# Connector.net
KiCad netlist of a schematic drawn in Altium Designer
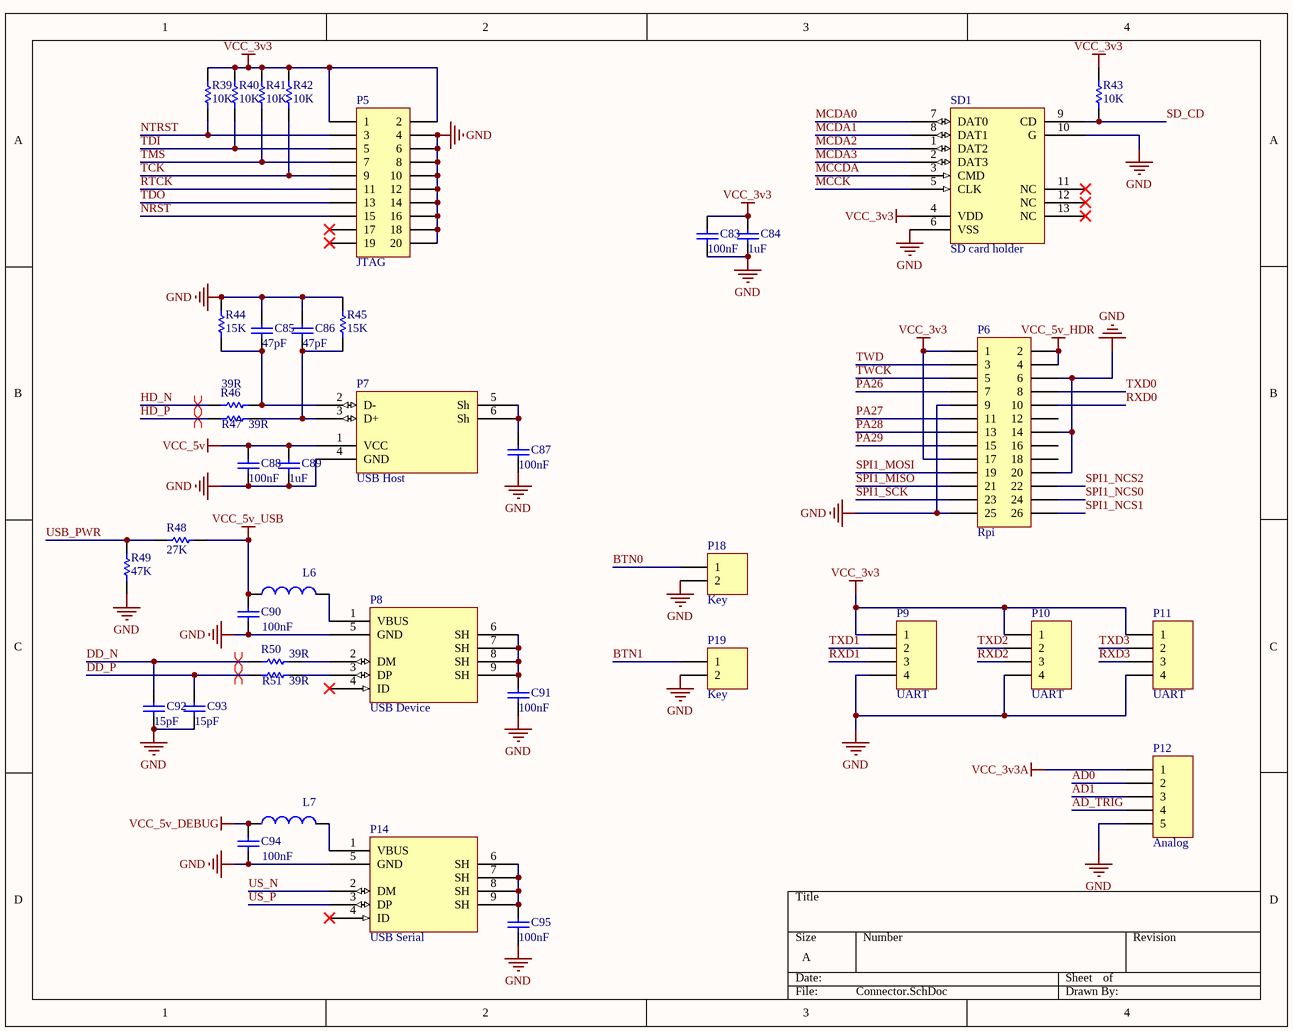
[diagram p0: Connector.SchDoc]

(export (version "E")
  (design (tool "Eeschema 10.0.6"))
  (components
    (comp (ref "C83")
      (value "100nF")
      (footprint "C0805")
      (description "Capacitor")
      (fields (field (name "Comment") "Cap") (field (name "PUBLISHER") "Altium Limited"))
      (libsource (lib "Miscellaneous Devices") (part "Cap"))
    )
    (comp (ref "C84")
      (value "1uF")
      (footprint "C0805")
      (description "Capacitor")
      (fields (field (name "Comment") "Cap") (field (name "PUBLISHER") "Altium Limited"))
      (libsource (lib "Miscellaneous Devices") (part "Cap"))
    )
    (comp (ref "C85")
      (value "47pF")
      (footprint "C0805")
      (description "Capacitor")
      (fields (field (name "Comment") "Cap") (field (name "PUBLISHER") "Altium Limited"))
      (libsource (lib "Miscellaneous Devices") (part "Cap"))
    )
    (comp (ref "C86")
      (value "47pF")
      (footprint "C0805")
      (description "Capacitor")
      (fields (field (name "Comment") "Cap") (field (name "PUBLISHER") "Altium Limited"))
      (libsource (lib "Miscellaneous Devices") (part "Cap"))
    )
    (comp (ref "C87")
      (value "100nF")
      (footprint "C0805")
      (description "Capacitor")
      (fields (field (name "Comment") "Cap") (field (name "PUBLISHER") "Altium Limited"))
      (libsource (lib "Miscellaneous Devices") (part "Cap"))
    )
    (comp (ref "C88")
      (value "100nF")
      (footprint "C0805")
      (description "Capacitor")
      (fields (field (name "Comment") "Cap") (field (name "PUBLISHER") "Altium Limited"))
      (libsource (lib "Miscellaneous Devices") (part "Cap"))
    )
    (comp (ref "C89")
      (value "1uF")
      (footprint "C0805")
      (description "Capacitor")
      (fields (field (name "Comment") "Cap") (field (name "PUBLISHER") "Altium Limited"))
      (libsource (lib "Miscellaneous Devices") (part "Cap"))
    )
    (comp (ref "C90")
      (value "100nF")
      (footprint "C0805")
      (description "Capacitor")
      (fields (field (name "Comment") "Cap") (field (name "PUBLISHER") "Altium Limited"))
      (libsource (lib "Miscellaneous Devices") (part "Cap"))
    )
    (comp (ref "C91")
      (value "100nF")
      (footprint "C0805")
      (description "Capacitor")
      (fields (field (name "Comment") "Cap") (field (name "PUBLISHER") "Altium Limited"))
      (libsource (lib "Miscellaneous Devices") (part "Cap"))
    )
    (comp (ref "C92")
      (value "15pF")
      (footprint "C0805")
      (description "Capacitor")
      (fields (field (name "Comment") "Cap") (field (name "PUBLISHER") "Altium Limited"))
      (libsource (lib "Miscellaneous Devices") (part "Cap"))
    )
    (comp (ref "C93")
      (value "15pF")
      (footprint "C0805")
      (description "Capacitor")
      (fields (field (name "Comment") "Cap") (field (name "PUBLISHER") "Altium Limited"))
      (libsource (lib "Miscellaneous Devices") (part "Cap"))
    )
    (comp (ref "C94")
      (value "100nF")
      (footprint "C0805")
      (description "Capacitor")
      (fields (field (name "Comment") "Cap") (field (name "PUBLISHER") "Altium Limited"))
      (libsource (lib "Miscellaneous Devices") (part "Cap"))
    )
    (comp (ref "C95")
      (value "100nF")
      (footprint "C0805")
      (description "Capacitor")
      (fields (field (name "Comment") "Cap") (field (name "PUBLISHER") "Altium Limited"))
      (libsource (lib "Miscellaneous Devices") (part "Cap"))
    )
    (comp (ref "L6")
      (value "Ferrite Bead")
      (footprint "C0805")
      (description "Inductor")
      (fields (field (name "PUBLISHER") "Altium Limited"))
      (libsource (lib "Miscellaneous Devices") (part "Inductor"))
    )
    (comp (ref "L7")
      (value "Ferrite Bead")
      (footprint "C0805")
      (description "Inductor")
      (fields (field (name "PUBLISHER") "Altium Limited"))
      (libsource (lib "Miscellaneous Devices") (part "Inductor"))
    )
    (comp (ref "P5")
      (value "JTAG")
      (footprint "IDC_2X10")
      (description "Header, 10-Pin, Dual row")
      (fields (field (name "PUBLISHER") "Altium Limited"))
      (libsource (lib "Miscellaneous Connectors") (part "Header 10X2"))
    )
    (comp (ref "P6")
      (value "Rpi")
      (footprint "HDR2X13")
      (description "Header, 13-Pin, Dual row")
      (fields (field (name "PUBLISHER") "Altium Limited"))
      (libsource (lib "Miscellaneous Connectors") (part "Header 13X2"))
    )
    (comp (ref "P7")
      (value "USB Host")
      (footprint "USB_Female")
      (libsource (lib "Connector_IntLib") (part "USB Host"))
    )
    (comp (ref "P8")
      (value "USB Device")
      (footprint "Mini USB")
      (libsource (lib "Connector_IntLib") (part "Mini USB"))
    )
    (comp (ref "P9")
      (value "UART")
      (footprint "XH_4pin")
      (description "Header, 4-Pin")
      (fields (field (name "PUBLISHER") "Altium Limited"))
      (libsource (lib "Miscellaneous Connectors") (part "Header 4"))
    )
    (comp (ref "P10")
      (value "UART")
      (footprint "XH_4pin")
      (description "Header, 4-Pin")
      (fields (field (name "PUBLISHER") "Altium Limited"))
      (libsource (lib "Miscellaneous Connectors") (part "Header 4"))
    )
    (comp (ref "P11")
      (value "UART")
      (footprint "XH_4pin")
      (description "Header, 4-Pin")
      (fields (field (name "PUBLISHER") "Altium Limited"))
      (libsource (lib "Miscellaneous Connectors") (part "Header 4"))
    )
    (comp (ref "P12")
      (value "Analog")
      (footprint "XH_5pin")
      (description "Header, 5-Pin")
      (fields (field (name "PUBLISHER") "Altium Limited"))
      (libsource (lib "Miscellaneous Connectors") (part "Header 5"))
    )
    (comp (ref "P14")
      (value "USB Serial")
      (footprint "Mini USB")
      (libsource (lib "Connector_IntLib") (part "Mini USB"))
    )
    (comp (ref "P18")
      (value "Key")
      (footprint "HDR1X2")
      (description "Header, 2-Pin")
      (fields (field (name "PUBLISHER") "Altium Limited"))
      (libsource (lib "Miscellaneous Connectors") (part "Header 2"))
    )
    (comp (ref "P19")
      (value "Key")
      (footprint "HDR1X2")
      (description "Header, 2-Pin")
      (fields (field (name "PUBLISHER") "Altium Limited"))
      (libsource (lib "Miscellaneous Connectors") (part "Header 2"))
    )
    (comp (ref "R39")
      (value "10K")
      (footprint "C0805")
      (description "Semiconductor Resistor")
      (fields (field (name "Comment") "Res Semi") (field (name "PUBLISHER") "Altium Limited"))
      (libsource (lib "Miscellaneous Devices") (part "Res Semi"))
    )
    (comp (ref "R40")
      (value "10K")
      (footprint "C0805")
      (description "Semiconductor Resistor")
      (fields (field (name "Comment") "Res Semi") (field (name "PUBLISHER") "Altium Limited"))
      (libsource (lib "Miscellaneous Devices") (part "Res Semi"))
    )
    (comp (ref "R41")
      (value "10K")
      (footprint "C0805")
      (description "Semiconductor Resistor")
      (fields (field (name "Comment") "Res Semi") (field (name "PUBLISHER") "Altium Limited"))
      (libsource (lib "Miscellaneous Devices") (part "Res Semi"))
    )
    (comp (ref "R42")
      (value "10K")
      (footprint "C0805")
      (description "Semiconductor Resistor")
      (fields (field (name "Comment") "Res Semi") (field (name "PUBLISHER") "Altium Limited"))
      (libsource (lib "Miscellaneous Devices") (part "Res Semi"))
    )
    (comp (ref "R43")
      (value "10K")
      (footprint "C0805")
      (description "Semiconductor Resistor")
      (fields (field (name "Comment") "Res Semi") (field (name "PUBLISHER") "Altium Limited"))
      (libsource (lib "Miscellaneous Devices") (part "Res Semi"))
    )
    (comp (ref "R44")
      (value "15K")
      (footprint "C0805")
      (description "Semiconductor Resistor")
      (fields (field (name "Comment") "Res Semi") (field (name "PUBLISHER") "Altium Limited"))
      (libsource (lib "Miscellaneous Devices") (part "Res Semi"))
    )
    (comp (ref "R45")
      (value "15K")
      (footprint "C0805")
      (description "Semiconductor Resistor")
      (fields (field (name "Comment") "Res Semi") (field (name "PUBLISHER") "Altium Limited"))
      (libsource (lib "Miscellaneous Devices") (part "Res Semi"))
    )
    (comp (ref "R46")
      (value "39R")
      (footprint "C0805")
      (description "Semiconductor Resistor")
      (fields (field (name "Comment") "Res Semi") (field (name "PUBLISHER") "Altium Limited"))
      (libsource (lib "Miscellaneous Devices") (part "Res Semi"))
    )
    (comp (ref "R47")
      (value "39R")
      (footprint "C0805")
      (description "Semiconductor Resistor")
      (fields (field (name "Comment") "Res Semi") (field (name "PUBLISHER") "Altium Limited"))
      (libsource (lib "Miscellaneous Devices") (part "Res Semi"))
    )
    (comp (ref "R48")
      (value "27K")
      (footprint "C0805")
      (description "Semiconductor Resistor")
      (fields (field (name "Comment") "Res Semi") (field (name "PUBLISHER") "Altium Limited"))
      (libsource (lib "Miscellaneous Devices") (part "Res Semi"))
    )
    (comp (ref "R49")
      (value "47K")
      (footprint "C0805")
      (description "Semiconductor Resistor")
      (fields (field (name "Comment") "Res Semi") (field (name "PUBLISHER") "Altium Limited"))
      (libsource (lib "Miscellaneous Devices") (part "Res Semi"))
    )
    (comp (ref "R50")
      (value "39R")
      (footprint "C0805")
      (description "Semiconductor Resistor")
      (fields (field (name "Comment") "Res Semi") (field (name "PUBLISHER") "Altium Limited"))
      (libsource (lib "Miscellaneous Devices") (part "Res Semi"))
    )
    (comp (ref "R51")
      (value "39R")
      (footprint "C0805")
      (description "Semiconductor Resistor")
      (fields (field (name "Comment") "Res Semi") (field (name "PUBLISHER") "Altium Limited"))
      (libsource (lib "Miscellaneous Devices") (part "Res Semi"))
    )
    (comp (ref "SD1")
      (value "SD card holder")
      (footprint "MicroSD socket")
      (libsource (lib "Connector_IntLib") (part "MicroSD_holder"))
    )
  )
  (nets
    (net (code "1") (name "/AD0") (class "Default")
      (node (ref "P12") (pin "2") (pinfunction "2_2") (pintype "passive"))
    )
    (net (code "2") (name "/AD1") (class "Default")
      (node (ref "P12") (pin "3") (pinfunction "3_3") (pintype "passive"))
    )
    (net (code "3") (name "/AD_TRIG") (class "Default")
      (node (ref "P12") (pin "4") (pinfunction "4_4") (pintype "passive"))
    )
    (net (code "4") (name "/BTN0") (class "Default")
      (node (ref "P18") (pin "1") (pinfunction "1_1") (pintype "passive"))
    )
    (net (code "5") (name "/BTN1") (class "Default")
      (node (ref "P19") (pin "1") (pinfunction "1_1") (pintype "passive"))
    )
    (net (code "6") (name "/DD_N") (class "Default")
      (node (ref "C92") (pin "2") (pinfunction "2_2") (pintype "passive"))
      (node (ref "R50") (pin "1") (pinfunction "1_1") (pintype "passive"))
    )
    (net (code "7") (name "/DD_P") (class "Default")
      (node (ref "C93") (pin "2") (pinfunction "2_2") (pintype "passive"))
      (node (ref "R51") (pin "1") (pinfunction "1_1") (pintype "passive"))
    )
    (net (code "8") (name "/HD_N") (class "Default")
      (node (ref "R46") (pin "1") (pinfunction "1_1") (pintype "passive"))
    )
    (net (code "9") (name "/HD_P") (class "Default")
      (node (ref "R47") (pin "1") (pinfunction "1_1") (pintype "passive"))
    )
    (net (code "10") (name "/MCCDA") (class "Default")
      (node (ref "SD1") (pin "3") (pinfunction "CMD_3") (pintype "input"))
    )
    (net (code "11") (name "/MCCK") (class "Default")
      (node (ref "SD1") (pin "5") (pinfunction "CLK_5") (pintype "input"))
    )
    (net (code "12") (name "/MCDA0") (class "Default")
      (node (ref "SD1") (pin "7") (pinfunction "DAT0_7") (pintype "bidirectional"))
    )
    (net (code "13") (name "/MCDA1") (class "Default")
      (node (ref "SD1") (pin "8") (pinfunction "DAT1_8") (pintype "bidirectional"))
    )
    (net (code "14") (name "/MCDA2") (class "Default")
      (node (ref "SD1") (pin "1") (pinfunction "DAT2_1") (pintype "bidirectional"))
    )
    (net (code "15") (name "/MCDA3") (class "Default")
      (node (ref "SD1") (pin "2") (pinfunction "DAT3_2") (pintype "bidirectional"))
    )
    (net (code "16") (name "/NRST") (class "Default")
      (node (ref "P5") (pin "15") (pinfunction "15_15") (pintype "passive"))
    )
    (net (code "17") (name "/NTRST") (class "Default")
      (node (ref "P5") (pin "3") (pinfunction "3_3") (pintype "passive"))
      (node (ref "R39") (pin "2") (pinfunction "2_2") (pintype "passive"))
    )
    (net (code "18") (name "/PA26") (class "Default")
      (node (ref "P6") (pin "7") (pinfunction "7_7") (pintype "passive"))
    )
    (net (code "19") (name "/PA27") (class "Default")
      (node (ref "P6") (pin "11") (pinfunction "11_11") (pintype "passive"))
    )
    (net (code "20") (name "/PA28") (class "Default")
      (node (ref "P6") (pin "13") (pinfunction "13_13") (pintype "passive"))
    )
    (net (code "21") (name "/PA29") (class "Default")
      (node (ref "P6") (pin "15") (pinfunction "15_15") (pintype "passive"))
    )
    (net (code "22") (name "/RTCK") (class "Default")
      (node (ref "P5") (pin "11") (pinfunction "11_11") (pintype "passive"))
    )
    (net (code "23") (name "/RXD0") (class "Default")
      (node (ref "P6") (pin "10") (pinfunction "10_10") (pintype "passive"))
    )
    (net (code "24") (name "/RXD1") (class "Default")
      (node (ref "P9") (pin "3") (pinfunction "3_3") (pintype "passive"))
    )
    (net (code "25") (name "/RXD2") (class "Default")
      (node (ref "P10") (pin "3") (pinfunction "3_3") (pintype "passive"))
    )
    (net (code "26") (name "/RXD3") (class "Default")
      (node (ref "P11") (pin "3") (pinfunction "3_3") (pintype "passive"))
    )
    (net (code "27") (name "/SD_CD") (class "Default")
      (node (ref "R43") (pin "2") (pinfunction "2_2") (pintype "passive"))
      (node (ref "SD1") (pin "9") (pinfunction "CD_9") (pintype "passive"))
    )
    (net (code "28") (name "/SPI1_MISO") (class "Default")
      (node (ref "P6") (pin "21") (pinfunction "21_21") (pintype "passive"))
    )
    (net (code "29") (name "/SPI1_MOSI") (class "Default")
      (node (ref "P6") (pin "19") (pinfunction "19_19") (pintype "passive"))
    )
    (net (code "30") (name "/SPI1_NCS0") (class "Default")
      (node (ref "P6") (pin "24") (pinfunction "24_24") (pintype "passive"))
    )
    (net (code "31") (name "/SPI1_NCS1") (class "Default")
      (node (ref "P6") (pin "26") (pinfunction "26_26") (pintype "passive"))
    )
    (net (code "32") (name "/SPI1_NCS2") (class "Default")
      (node (ref "P6") (pin "22") (pinfunction "22_22") (pintype "passive"))
    )
    (net (code "33") (name "/SPI1_SCK") (class "Default")
      (node (ref "P6") (pin "23") (pinfunction "23_23") (pintype "passive"))
    )
    (net (code "34") (name "/TCK") (class "Default")
      (node (ref "P5") (pin "9") (pinfunction "9_9") (pintype "passive"))
      (node (ref "R42") (pin "2") (pinfunction "2_2") (pintype "passive"))
    )
    (net (code "35") (name "/TDI") (class "Default")
      (node (ref "P5") (pin "5") (pinfunction "5_5") (pintype "passive"))
      (node (ref "R40") (pin "2") (pinfunction "2_2") (pintype "passive"))
    )
    (net (code "36") (name "/TDO") (class "Default")
      (node (ref "P5") (pin "13") (pinfunction "13_13") (pintype "passive"))
    )
    (net (code "37") (name "/TMS") (class "Default")
      (node (ref "P5") (pin "7") (pinfunction "7_7") (pintype "passive"))
      (node (ref "R41") (pin "2") (pinfunction "2_2") (pintype "passive"))
    )
    (net (code "38") (name "/TWCK") (class "Default")
      (node (ref "P6") (pin "5") (pinfunction "5_5") (pintype "passive"))
    )
    (net (code "39") (name "/TWD") (class "Default")
      (node (ref "P6") (pin "3") (pinfunction "3_3") (pintype "passive"))
    )
    (net (code "40") (name "/TXD0") (class "Default")
      (node (ref "P6") (pin "8") (pinfunction "8_8") (pintype "passive"))
    )
    (net (code "41") (name "/TXD1") (class "Default")
      (node (ref "P9") (pin "2") (pinfunction "2_2") (pintype "passive"))
    )
    (net (code "42") (name "/TXD2") (class "Default")
      (node (ref "P10") (pin "2") (pinfunction "2_2") (pintype "passive"))
    )
    (net (code "43") (name "/TXD3") (class "Default")
      (node (ref "P11") (pin "2") (pinfunction "2_2") (pintype "passive"))
    )
    (net (code "44") (name "/USB_PWR") (class "Default")
      (node (ref "R48") (pin "2") (pinfunction "2_2") (pintype "passive"))
      (node (ref "R49") (pin "1") (pinfunction "1_1") (pintype "passive"))
    )
    (net (code "45") (name "/US_N") (class "Default")
      (node (ref "P14") (pin "2") (pinfunction "DM_2") (pintype "bidirectional"))
    )
    (net (code "46") (name "/US_P") (class "Default")
      (node (ref "P14") (pin "3") (pinfunction "DP_3") (pintype "bidirectional"))
    )
    (net (code "47") (name "GND") (class "Default")
      (node (ref "C83") (pin "1") (pinfunction "1_1") (pintype "passive"))
      (node (ref "C84") (pin "1") (pinfunction "1_1") (pintype "passive"))
      (node (ref "C85") (pin "2") (pinfunction "2_2") (pintype "passive"))
      (node (ref "C86") (pin "2") (pinfunction "2_2") (pintype "passive"))
      (node (ref "C87") (pin "1") (pinfunction "1_1") (pintype "passive"))
      (node (ref "C88") (pin "1") (pinfunction "1_1") (pintype "passive"))
      (node (ref "C89") (pin "1") (pinfunction "1_1") (pintype "passive"))
      (node (ref "C90") (pin "1") (pinfunction "1_1") (pintype "passive"))
      (node (ref "C91") (pin "1") (pinfunction "1_1") (pintype "passive"))
      (node (ref "C92") (pin "1") (pinfunction "1_1") (pintype "passive"))
      (node (ref "C93") (pin "1") (pinfunction "1_1") (pintype "passive"))
      (node (ref "C94") (pin "1") (pinfunction "1_1") (pintype "passive"))
      (node (ref "C95") (pin "1") (pinfunction "1_1") (pintype "passive"))
      (node (ref "P10") (pin "4") (pinfunction "4_4") (pintype "passive"))
      (node (ref "P11") (pin "4") (pinfunction "4_4") (pintype "passive"))
      (node (ref "P12") (pin "5") (pinfunction "5_5") (pintype "passive"))
      (node (ref "P14") (pin "5") (pinfunction "GND_5") (pintype "power_in"))
      (node (ref "P18") (pin "2") (pinfunction "2_2") (pintype "passive"))
      (node (ref "P19") (pin "2") (pinfunction "2_2") (pintype "passive"))
      (node (ref "P5") (pin "10") (pinfunction "10_10") (pintype "passive"))
      (node (ref "P5") (pin "12") (pinfunction "12_12") (pintype "passive"))
      (node (ref "P5") (pin "14") (pinfunction "14_14") (pintype "passive"))
      (node (ref "P5") (pin "16") (pinfunction "16_16") (pintype "passive"))
      (node (ref "P5") (pin "18") (pinfunction "18_18") (pintype "passive"))
      (node (ref "P5") (pin "20") (pinfunction "20_20") (pintype "passive"))
      (node (ref "P5") (pin "4") (pinfunction "4_4") (pintype "passive"))
      (node (ref "P5") (pin "6") (pinfunction "6_6") (pintype "passive"))
      (node (ref "P5") (pin "8") (pinfunction "8_8") (pintype "passive"))
      (node (ref "P6") (pin "14") (pinfunction "14_14") (pintype "passive"))
      (node (ref "P6") (pin "20") (pinfunction "20_20") (pintype "passive"))
      (node (ref "P6") (pin "25") (pinfunction "25_25") (pintype "passive"))
      (node (ref "P6") (pin "6") (pinfunction "6_6") (pintype "passive"))
      (node (ref "P6") (pin "9") (pinfunction "9_9") (pintype "passive"))
      (node (ref "P7") (pin "4") (pinfunction "GND_4") (pintype "power_in"))
      (node (ref "P8") (pin "5") (pinfunction "GND_5") (pintype "power_in"))
      (node (ref "P9") (pin "4") (pinfunction "4_4") (pintype "passive"))
      (node (ref "R44") (pin "1") (pinfunction "1_1") (pintype "passive"))
      (node (ref "R45") (pin "1") (pinfunction "1_1") (pintype "passive"))
      (node (ref "R49") (pin "2") (pinfunction "2_2") (pintype "passive"))
      (node (ref "SD1") (pin "10") (pinfunction "G_10") (pintype "passive"))
      (node (ref "SD1") (pin "6") (pinfunction "VSS_6") (pintype "power_in"))
    )
    (net (code "48") (name "Net-(C87-Pad2)") (class "Default")
      (node (ref "C87") (pin "2") (pinfunction "2_2") (pintype "passive"))
      (node (ref "P7") (pin "5") (pinfunction "Sh_5") (pintype "passive"))
      (node (ref "P7") (pin "6") (pinfunction "Sh_6") (pintype "passive"))
    )
    (net (code "49") (name "Net-(C91-Pad2)") (class "Default")
      (node (ref "C91") (pin "2") (pinfunction "2_2") (pintype "passive"))
      (node (ref "P8") (pin "6") (pinfunction "SH_6") (pintype "passive"))
      (node (ref "P8") (pin "7") (pinfunction "SH_7") (pintype "passive"))
      (node (ref "P8") (pin "8") (pinfunction "SH_8") (pintype "passive"))
      (node (ref "P8") (pin "9") (pinfunction "SH_9") (pintype "passive"))
    )
    (net (code "50") (name "Net-(C95-Pad2)") (class "Default")
      (node (ref "C95") (pin "2") (pinfunction "2_2") (pintype "passive"))
      (node (ref "P14") (pin "6") (pinfunction "SH_6") (pintype "passive"))
      (node (ref "P14") (pin "7") (pinfunction "SH_7") (pintype "passive"))
      (node (ref "P14") (pin "8") (pinfunction "SH_8") (pintype "passive"))
      (node (ref "P14") (pin "9") (pinfunction "SH_9") (pintype "passive"))
    )
    (net (code "51") (name "Net-(P7-D+)") (class "Default")
      (node (ref "C86") (pin "1") (pinfunction "1_1") (pintype "passive"))
      (node (ref "P7") (pin "3") (pinfunction "D+_3") (pintype "bidirectional"))
      (node (ref "R45") (pin "2") (pinfunction "2_2") (pintype "passive"))
      (node (ref "R47") (pin "2") (pinfunction "2_2") (pintype "passive"))
    )
    (net (code "52") (name "Net-(P7-D-)") (class "Default")
      (node (ref "C85") (pin "1") (pinfunction "1_1") (pintype "passive"))
      (node (ref "P7") (pin "2") (pinfunction "D-_2") (pintype "bidirectional"))
      (node (ref "R44") (pin "2") (pinfunction "2_2") (pintype "passive"))
      (node (ref "R46") (pin "2") (pinfunction "2_2") (pintype "passive"))
    )
    (net (code "53") (name "Net-(P8-DM)") (class "Default")
      (node (ref "P8") (pin "2") (pinfunction "DM_2") (pintype "bidirectional"))
      (node (ref "R50") (pin "2") (pinfunction "2_2") (pintype "passive"))
    )
    (net (code "54") (name "Net-(P8-DP)") (class "Default")
      (node (ref "P8") (pin "3") (pinfunction "DP_3") (pintype "bidirectional"))
      (node (ref "R51") (pin "2") (pinfunction "2_2") (pintype "passive"))
    )
    (net (code "55") (name "Net-(P8-VBUS)") (class "Default")
      (node (ref "L6") (pin "2") (pinfunction "2_2") (pintype "passive"))
      (node (ref "P8") (pin "1") (pinfunction "VBUS_1") (pintype "power_in"))
    )
    (net (code "56") (name "Net-(P14-VBUS)") (class "Default")
      (node (ref "L7") (pin "2") (pinfunction "2_2") (pintype "passive"))
      (node (ref "P14") (pin "1") (pinfunction "VBUS_1") (pintype "power_in"))
    )
    (net (code "57") (name "VCC_3v3") (class "Default")
      (node (ref "C83") (pin "2") (pinfunction "2_2") (pintype "passive"))
      (node (ref "C84") (pin "2") (pinfunction "2_2") (pintype "passive"))
      (node (ref "P10") (pin "1") (pinfunction "1_1") (pintype "passive"))
      (node (ref "P11") (pin "1") (pinfunction "1_1") (pintype "passive"))
      (node (ref "P5") (pin "1") (pinfunction "1_1") (pintype "passive"))
      (node (ref "P5") (pin "2") (pinfunction "2_2") (pintype "passive"))
      (node (ref "P6") (pin "1") (pinfunction "1_1") (pintype "passive"))
      (node (ref "P6") (pin "17") (pinfunction "17_17") (pintype "passive"))
      (node (ref "P9") (pin "1") (pinfunction "1_1") (pintype "passive"))
      (node (ref "R39") (pin "1") (pinfunction "1_1") (pintype "passive"))
      (node (ref "R40") (pin "1") (pinfunction "1_1") (pintype "passive"))
      (node (ref "R41") (pin "1") (pinfunction "1_1") (pintype "passive"))
      (node (ref "R42") (pin "1") (pinfunction "1_1") (pintype "passive"))
      (node (ref "R43") (pin "1") (pinfunction "1_1") (pintype "passive"))
      (node (ref "SD1") (pin "4") (pinfunction "VDD_4") (pintype "power_in"))
    )
    (net (code "58") (name "VCC_3v3A") (class "Default")
      (node (ref "P12") (pin "1") (pinfunction "1_1") (pintype "passive"))
    )
    (net (code "59") (name "VCC_5v") (class "Default")
      (node (ref "C88") (pin "2") (pinfunction "2_2") (pintype "passive"))
      (node (ref "C89") (pin "2") (pinfunction "2_2") (pintype "passive"))
      (node (ref "P7") (pin "1") (pinfunction "VCC_1") (pintype "power_in"))
    )
    (net (code "60") (name "VCC_5v_DEBUG") (class "Default")
      (node (ref "C94") (pin "2") (pinfunction "2_2") (pintype "passive"))
      (node (ref "L7") (pin "1") (pinfunction "1_1") (pintype "passive"))
    )
    (net (code "61") (name "VCC_5v_HDR") (class "Default")
      (node (ref "P6") (pin "2") (pinfunction "2_2") (pintype "passive"))
      (node (ref "P6") (pin "4") (pinfunction "4_4") (pintype "passive"))
    )
    (net (code "62") (name "VCC_5v_USB") (class "Default")
      (node (ref "C90") (pin "2") (pinfunction "2_2") (pintype "passive"))
      (node (ref "L6") (pin "1") (pinfunction "1_1") (pintype "passive"))
      (node (ref "R48") (pin "1") (pinfunction "1_1") (pintype "passive"))
    )
    (net (code "63") (name "unconnected-(P5-Pad17)") (class "Default")
      (node (ref "P5") (pin "17") (pinfunction "17_17") (pintype "passive+no_connect"))
    )
    (net (code "64") (name "unconnected-(P5-Pad19)") (class "Default")
      (node (ref "P5") (pin "19") (pinfunction "19_19") (pintype "passive+no_connect"))
    )
    (net (code "65") (name "unconnected-(P6-Pad12)") (class "Default")
      (node (ref "P6") (pin "12") (pinfunction "12_12") (pintype "passive"))
    )
    (net (code "66") (name "unconnected-(P6-Pad16)") (class "Default")
      (node (ref "P6") (pin "16") (pinfunction "16_16") (pintype "passive"))
    )
    (net (code "67") (name "unconnected-(P6-Pad18)") (class "Default")
      (node (ref "P6") (pin "18") (pinfunction "18_18") (pintype "passive"))
    )
    (net (code "68") (name "unconnected-(P8-ID-Pad4)") (class "Default")
      (node (ref "P8") (pin "4") (pinfunction "ID_4") (pintype "input+no_connect"))
    )
    (net (code "69") (name "unconnected-(P14-ID-Pad4)") (class "Default")
      (node (ref "P14") (pin "4") (pinfunction "ID_4") (pintype "input+no_connect"))
    )
    (net (code "70") (name "unconnected-(SD1-NC-Pad11)") (class "Default")
      (node (ref "SD1") (pin "11") (pinfunction "NC_11") (pintype "passive+no_connect"))
    )
    (net (code "71") (name "unconnected-(SD1-NC-Pad12)") (class "Default")
      (node (ref "SD1") (pin "12") (pinfunction "NC_12") (pintype "passive+no_connect"))
    )
    (net (code "72") (name "unconnected-(SD1-NC-Pad13)") (class "Default")
      (node (ref "SD1") (pin "13") (pinfunction "NC_13") (pintype "passive+no_connect"))
    )
  )
)
